# Small_Mosfet.net
KiCad netlist of a schematic drawn in EAGLE
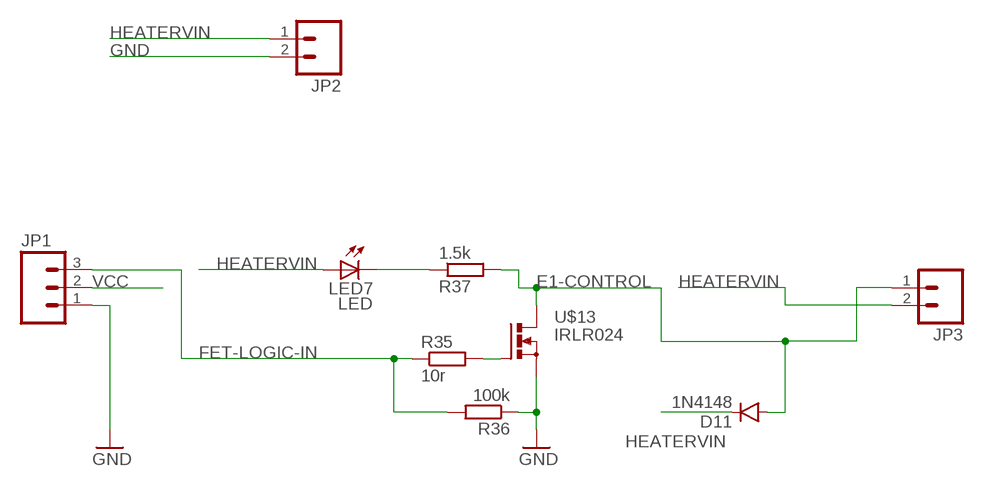
[diagram p0: schematic, sheet 1]

(export (version "E")
  (design (tool "Eeschema 10.0.6"))
  (components
    (comp (ref "D11")
      (value "1N4148")
      (footprint "eagle-import:SOD-323")
      (libsource (lib "eagle-import") (part "DIODEBAS16"))
    )
    (comp (ref "JP1")
      (value "M03LOCK")
      (footprint "eagle-import:1X03_LOCK")
      (libsource (lib "eagle-import") (part "M03LOCK"))
    )
    (comp (ref "JP2")
      (value "M023.5MM")
      (footprint "eagle-import:SCREWTERMINAL-3.5MM-2")
      (libsource (lib "eagle-import") (part "M023.5MM"))
    )
    (comp (ref "JP3")
      (value "M023.5MM")
      (footprint "eagle-import:SCREWTERMINAL-3.5MM-2")
      (libsource (lib "eagle-import") (part "M023.5MM"))
    )
    (comp (ref "LED7")
      (value "LED")
      (footprint "eagle-import:SML0603")
      (libsource (lib "eagle-import") (part "LEDSML0603"))
    )
    (comp (ref "R35")
      (value "10r")
      (footprint "eagle-import:R0603")
      (libsource (lib "eagle-import") (part "R-EU_R0603"))
    )
    (comp (ref "R36")
      (value "100k")
      (footprint "eagle-import:R0603")
      (libsource (lib "eagle-import") (part "R-EU_R0603"))
    )
    (comp (ref "R37")
      (value "1.5k")
      (footprint "eagle-import:R0603")
      (libsource (lib "eagle-import") (part "R-EU_R0603"))
    )
    (comp (ref "U$13")
      (value "IRLR024")
      (footprint "eagle-import:D-PAK_TO252AA")
      (libsource (lib "eagle-import") (part "N-POWER-MOSFETDPAK-MOSFET"))
    )
  )
  (nets
    (net (code "1") (name "/E1-CONTROL") (class "Default")
      (node (ref "D11") (pin "A") (pinfunction "A_A") (pintype "passive"))
      (node (ref "JP3") (pin "1") (pinfunction "1_1") (pintype "passive"))
      (node (ref "R37") (pin "2") (pinfunction "2_2") (pintype "passive"))
      (node (ref "U$13") (pin "4") (pinfunction "D_4") (pintype "passive"))
    )
    (net (code "2") (name "/FET-LOGIC-IN") (class "Default")
      (node (ref "JP1") (pin "3") (pinfunction "3_3") (pintype "passive"))
      (node (ref "R35") (pin "1") (pinfunction "1_1") (pintype "passive"))
      (node (ref "R36") (pin "2") (pinfunction "2_2") (pintype "passive"))
    )
    (net (code "3") (name "/HEATERVIN") (class "Default")
      (node (ref "D11") (pin "C") (pinfunction "C_C") (pintype "passive"))
      (node (ref "JP2") (pin "1") (pinfunction "1_1") (pintype "passive"))
      (node (ref "JP3") (pin "2") (pinfunction "2_2") (pintype "passive"))
      (node (ref "LED7") (pin "A") (pinfunction "A_A") (pintype "passive"))
    )
    (net (code "4") (name "/VCC") (class "Default")
      (node (ref "JP1") (pin "2") (pinfunction "2_2") (pintype "passive"))
    )
    (net (code "5") (name "GND") (class "Default")
      (node (ref "JP1") (pin "1") (pinfunction "1_1") (pintype "passive"))
      (node (ref "JP2") (pin "2") (pinfunction "2_2") (pintype "passive"))
      (node (ref "R36") (pin "1") (pinfunction "1_1") (pintype "passive"))
      (node (ref "U$13") (pin "3") (pinfunction "S_3") (pintype "passive"))
    )
    (net (code "6") (name "Net-(LED7-PadC)") (class "Default")
      (node (ref "LED7") (pin "C") (pinfunction "C_C") (pintype "passive"))
      (node (ref "R37") (pin "1") (pinfunction "1_1") (pintype "passive"))
    )
    (net (code "7") (name "Net-(U$13-G)") (class "Default")
      (node (ref "R35") (pin "2") (pinfunction "2_2") (pintype "passive"))
      (node (ref "U$13") (pin "1") (pinfunction "G_1") (pintype "passive"))
    )
  )
)
